# Ultrasonics.net
KiCad netlist of a schematic drawn in EAGLE
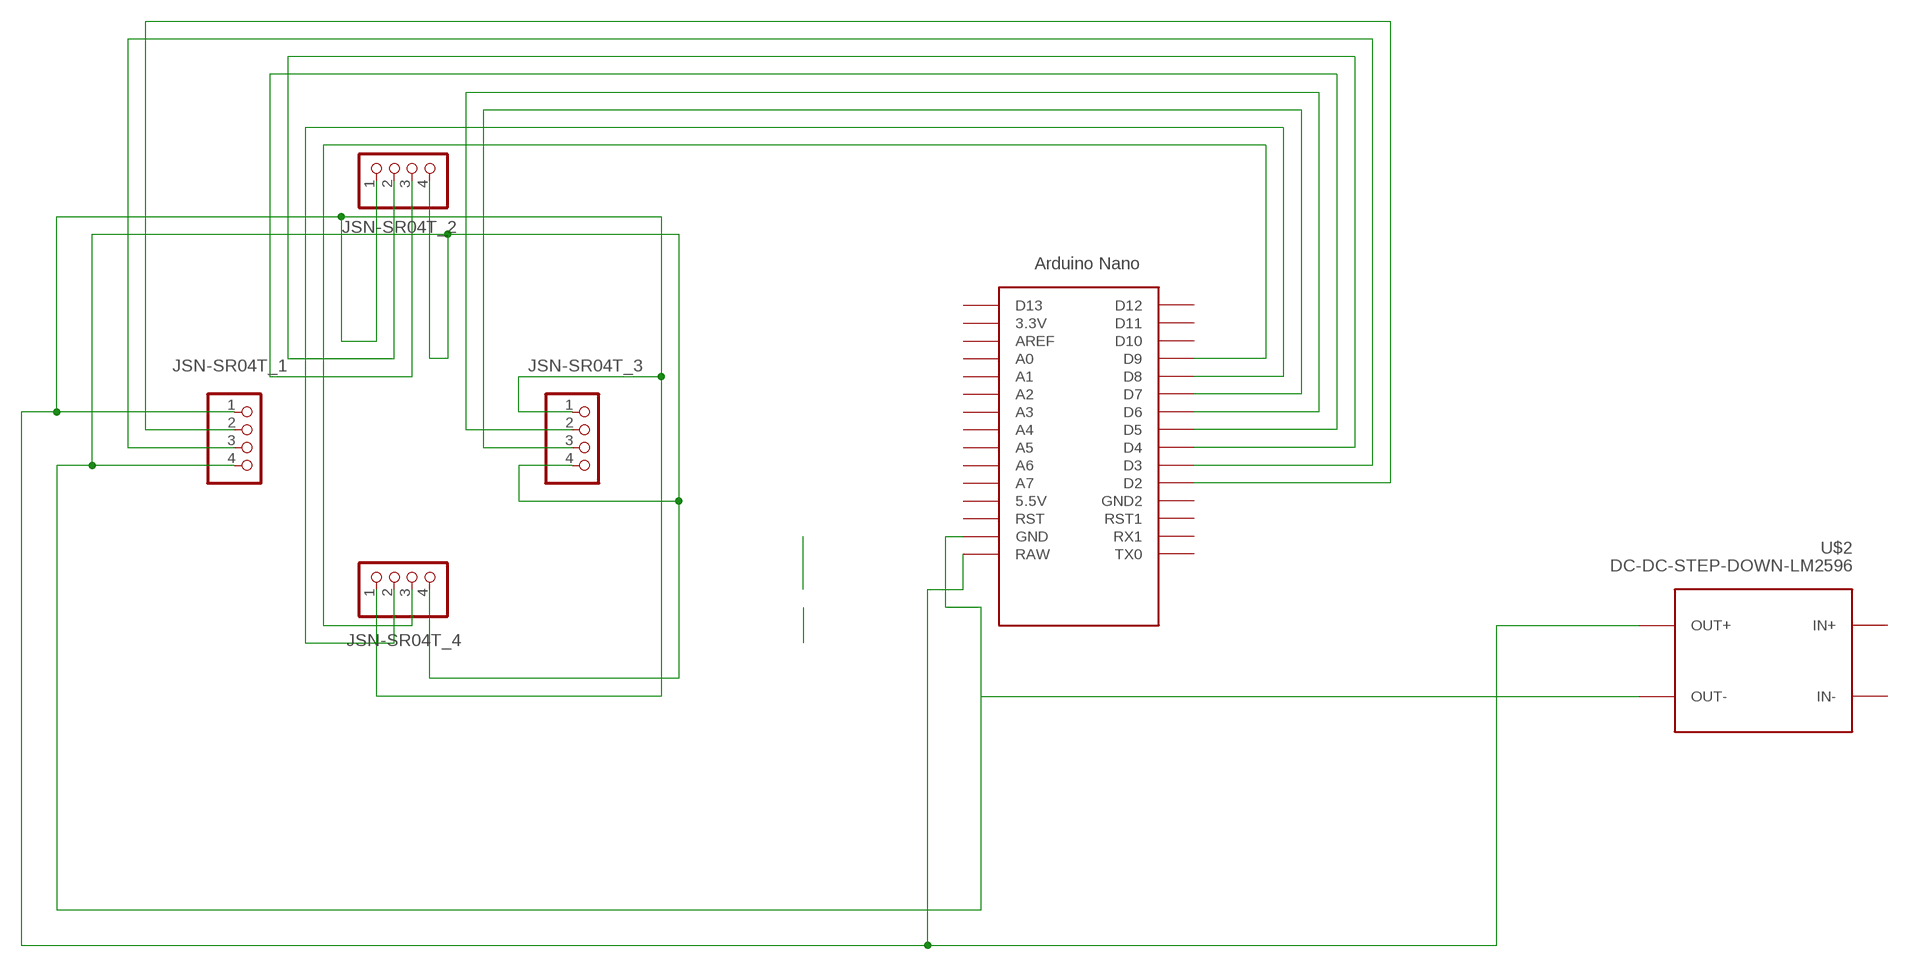
[diagram p0: schematic, sheet 1]

(export (version "E")
  (design (tool "Eeschema 10.0.6"))
  (components
    (comp (ref "JSN-SR04T_1")
      (value "PINHD-1X4")
      (footprint "eagle-import:1X04")
      (libsource (lib "eagle-import") (part "PINHD-1X4"))
    )
    (comp (ref "JSN-SR04T_2")
      (value "PINHD-1X4")
      (footprint "eagle-import:1X04")
      (libsource (lib "eagle-import") (part "PINHD-1X4"))
    )
    (comp (ref "JSN-SR04T_3")
      (value "PINHD-1X4")
      (footprint "eagle-import:1X04")
      (libsource (lib "eagle-import") (part "PINHD-1X4"))
    )
    (comp (ref "JSN-SR04T_4")
      (value "PINHD-1X4")
      (footprint "eagle-import:1X04")
      (libsource (lib "eagle-import") (part "PINHD-1X4"))
    )
    (comp (ref "U$1")
      (value "NANO")
      (footprint "eagle-import:NANO")
      (libsource (lib "eagle-import") (part "NANO"))
    )
    (comp (ref "U$2")
      (value "DC-DC-STEP-DOWN-LM2596")
      (footprint "eagle-import:DC-DC-STEP-DOWN-LM2596")
      (libsource (lib "eagle-import") (part "DC-DC-STEP-DOWN-LM2596"))
    )
  )
  (nets
    (net (code "1") (name "Net-(JSN-SR04T_1-Pad1)") (class "Default")
      (node (ref "JSN-SR04T_1") (pin "1") (pinfunction "1_1") (pintype "passive"))
      (node (ref "JSN-SR04T_2") (pin "1") (pinfunction "1_1") (pintype "passive"))
      (node (ref "JSN-SR04T_3") (pin "1") (pinfunction "1_1") (pintype "passive"))
      (node (ref "JSN-SR04T_4") (pin "1") (pinfunction "1_1") (pintype "passive"))
      (node (ref "U$1") (pin "RAW") (pinfunction "RAW_RAW") (pintype "bidirectional"))
      (node (ref "U$2") (pin "OUT+") (pinfunction "OUT+_OUT+") (pintype "bidirectional"))
    )
    (net (code "2") (name "Net-(JSN-SR04T_1-Pad2)") (class "Default")
      (node (ref "JSN-SR04T_1") (pin "2") (pinfunction "2_2") (pintype "passive"))
      (node (ref "U$1") (pin "D2") (pinfunction "D2_D2") (pintype "bidirectional"))
    )
    (net (code "3") (name "Net-(JSN-SR04T_1-Pad3)") (class "Default")
      (node (ref "JSN-SR04T_1") (pin "3") (pinfunction "3_3") (pintype "passive"))
      (node (ref "U$1") (pin "D3") (pinfunction "D3_D3") (pintype "bidirectional"))
    )
    (net (code "4") (name "Net-(JSN-SR04T_1-Pad4)") (class "Default")
      (node (ref "JSN-SR04T_1") (pin "4") (pinfunction "4_4") (pintype "passive"))
      (node (ref "JSN-SR04T_2") (pin "4") (pinfunction "4_4") (pintype "passive"))
      (node (ref "JSN-SR04T_3") (pin "4") (pinfunction "4_4") (pintype "passive"))
      (node (ref "JSN-SR04T_4") (pin "4") (pinfunction "4_4") (pintype "passive"))
      (node (ref "U$1") (pin "GND") (pinfunction "GND_GND") (pintype "bidirectional"))
      (node (ref "U$2") (pin "OUT-") (pinfunction "OUT-_OUT-") (pintype "bidirectional"))
    )
    (net (code "5") (name "Net-(JSN-SR04T_2-Pad2)") (class "Default")
      (node (ref "JSN-SR04T_2") (pin "2") (pinfunction "2_2") (pintype "passive"))
      (node (ref "U$1") (pin "D4") (pinfunction "D4_D4") (pintype "bidirectional"))
    )
    (net (code "6") (name "Net-(JSN-SR04T_2-Pad3)") (class "Default")
      (node (ref "JSN-SR04T_2") (pin "3") (pinfunction "3_3") (pintype "passive"))
      (node (ref "U$1") (pin "D5") (pinfunction "D5_D5") (pintype "bidirectional"))
    )
    (net (code "7") (name "Net-(JSN-SR04T_3-Pad2)") (class "Default")
      (node (ref "JSN-SR04T_3") (pin "2") (pinfunction "2_2") (pintype "passive"))
      (node (ref "U$1") (pin "D6") (pinfunction "D6_D6") (pintype "bidirectional"))
    )
    (net (code "8") (name "Net-(JSN-SR04T_3-Pad3)") (class "Default")
      (node (ref "JSN-SR04T_3") (pin "3") (pinfunction "3_3") (pintype "passive"))
      (node (ref "U$1") (pin "D7") (pinfunction "D7_D7") (pintype "bidirectional"))
    )
    (net (code "9") (name "Net-(JSN-SR04T_4-Pad2)") (class "Default")
      (node (ref "JSN-SR04T_4") (pin "2") (pinfunction "2_2") (pintype "passive"))
      (node (ref "U$1") (pin "D8") (pinfunction "D8_D8") (pintype "bidirectional"))
    )
    (net (code "10") (name "Net-(JSN-SR04T_4-Pad3)") (class "Default")
      (node (ref "JSN-SR04T_4") (pin "3") (pinfunction "3_3") (pintype "passive"))
      (node (ref "U$1") (pin "D9") (pinfunction "D9_D9") (pintype "bidirectional"))
    )
    (net (code "11") (name "unconnected-(U$1-5.5V-Pad5V)") (class "Default")
      (node (ref "U$1") (pin "5V") (pinfunction "5.5V_5V") (pintype "bidirectional"))
    )
    (net (code "12") (name "unconnected-(U$1-GND2-PadGND1)") (class "Default")
      (node (ref "U$1") (pin "GND1") (pinfunction "GND2_GND1") (pintype "bidirectional"))
    )
    (net (code "13") (name "unconnected-(U$1-Pad3.3V)") (class "Default")
      (node (ref "U$1") (pin "3.3V") (pinfunction "3.3V_3.3V") (pintype "bidirectional"))
    )
    (net (code "14") (name "unconnected-(U$1-PadA0)") (class "Default")
      (node (ref "U$1") (pin "A0") (pinfunction "A0_A0") (pintype "bidirectional"))
    )
    (net (code "15") (name "unconnected-(U$1-PadA1)") (class "Default")
      (node (ref "U$1") (pin "A1") (pinfunction "A1_A1") (pintype "bidirectional"))
    )
    (net (code "16") (name "unconnected-(U$1-PadA2)") (class "Default")
      (node (ref "U$1") (pin "A2") (pinfunction "A2_A2") (pintype "bidirectional"))
    )
    (net (code "17") (name "unconnected-(U$1-PadA3)") (class "Default")
      (node (ref "U$1") (pin "A3") (pinfunction "A3_A3") (pintype "bidirectional"))
    )
    (net (code "18") (name "unconnected-(U$1-PadA4)") (class "Default")
      (node (ref "U$1") (pin "A4") (pinfunction "A4_A4") (pintype "bidirectional"))
    )
    (net (code "19") (name "unconnected-(U$1-PadA5)") (class "Default")
      (node (ref "U$1") (pin "A5") (pinfunction "A5_A5") (pintype "bidirectional"))
    )
    (net (code "20") (name "unconnected-(U$1-PadA6)") (class "Default")
      (node (ref "U$1") (pin "A6") (pinfunction "A6_A6") (pintype "bidirectional"))
    )
    (net (code "21") (name "unconnected-(U$1-PadA7)") (class "Default")
      (node (ref "U$1") (pin "A7") (pinfunction "A7_A7") (pintype "bidirectional"))
    )
    (net (code "22") (name "unconnected-(U$1-PadAREF)") (class "Default")
      (node (ref "U$1") (pin "AREF") (pinfunction "AREF_AREF") (pintype "bidirectional"))
    )
    (net (code "23") (name "unconnected-(U$1-PadD10)") (class "Default")
      (node (ref "U$1") (pin "D10") (pinfunction "D10_D10") (pintype "bidirectional"))
    )
    (net (code "24") (name "unconnected-(U$1-PadD11)") (class "Default")
      (node (ref "U$1") (pin "D11") (pinfunction "D11_D11") (pintype "bidirectional"))
    )
    (net (code "25") (name "unconnected-(U$1-PadD12)") (class "Default")
      (node (ref "U$1") (pin "D12") (pinfunction "D12_D12") (pintype "bidirectional"))
    )
    (net (code "26") (name "unconnected-(U$1-PadD13)") (class "Default")
      (node (ref "U$1") (pin "D13") (pinfunction "D13_D13") (pintype "bidirectional"))
    )
    (net (code "27") (name "unconnected-(U$1-PadICSP1)") (class "Default")
      (node (ref "U$1") (pin "ICSP1") (pinfunction "ICSP1_ICSP1") (pintype "bidirectional"))
    )
    (net (code "28") (name "unconnected-(U$1-PadICSP2)") (class "Default")
      (node (ref "U$1") (pin "ICSP2") (pinfunction "ICSP2_ICSP2") (pintype "bidirectional"))
    )
    (net (code "29") (name "unconnected-(U$1-PadICSP3)") (class "Default")
      (node (ref "U$1") (pin "ICSP3") (pinfunction "ICSP3_ICSP3") (pintype "bidirectional"))
    )
    (net (code "30") (name "unconnected-(U$1-PadICSP4)") (class "Default")
      (node (ref "U$1") (pin "ICSP4") (pinfunction "ICSP4_ICSP4") (pintype "bidirectional"))
    )
    (net (code "31") (name "unconnected-(U$1-PadICSP5)") (class "Default")
      (node (ref "U$1") (pin "ICSP5") (pinfunction "ICSP5_ICSP5") (pintype "bidirectional"))
    )
    (net (code "32") (name "unconnected-(U$1-PadICSP6)") (class "Default")
      (node (ref "U$1") (pin "ICSP6") (pinfunction "ICSP6_ICSP6") (pintype "bidirectional"))
    )
    (net (code "33") (name "unconnected-(U$1-PadRST)") (class "Default")
      (node (ref "U$1") (pin "RST") (pinfunction "RST_RST") (pintype "bidirectional"))
    )
    (net (code "34") (name "unconnected-(U$1-PadRST1)") (class "Default")
      (node (ref "U$1") (pin "RST1") (pinfunction "RST1_RST1") (pintype "bidirectional"))
    )
    (net (code "35") (name "unconnected-(U$1-PadRX1)") (class "Default")
      (node (ref "U$1") (pin "RX1") (pinfunction "RX1_RX1") (pintype "bidirectional"))
    )
    (net (code "36") (name "unconnected-(U$1-PadTX0)") (class "Default")
      (node (ref "U$1") (pin "TX0") (pinfunction "TX0_TX0") (pintype "bidirectional"))
    )
    (net (code "37") (name "unconnected-(U$2-PadIN+)") (class "Default")
      (node (ref "U$2") (pin "IN+") (pinfunction "IN+_IN+") (pintype "bidirectional"))
    )
    (net (code "38") (name "unconnected-(U$2-PadIN-)") (class "Default")
      (node (ref "U$2") (pin "IN-") (pinfunction "IN-_IN-") (pintype "bidirectional"))
    )
  )
)
